# Battery_Load_Share_V1.net
KiCad netlist of a schematic drawn in Altium Designer
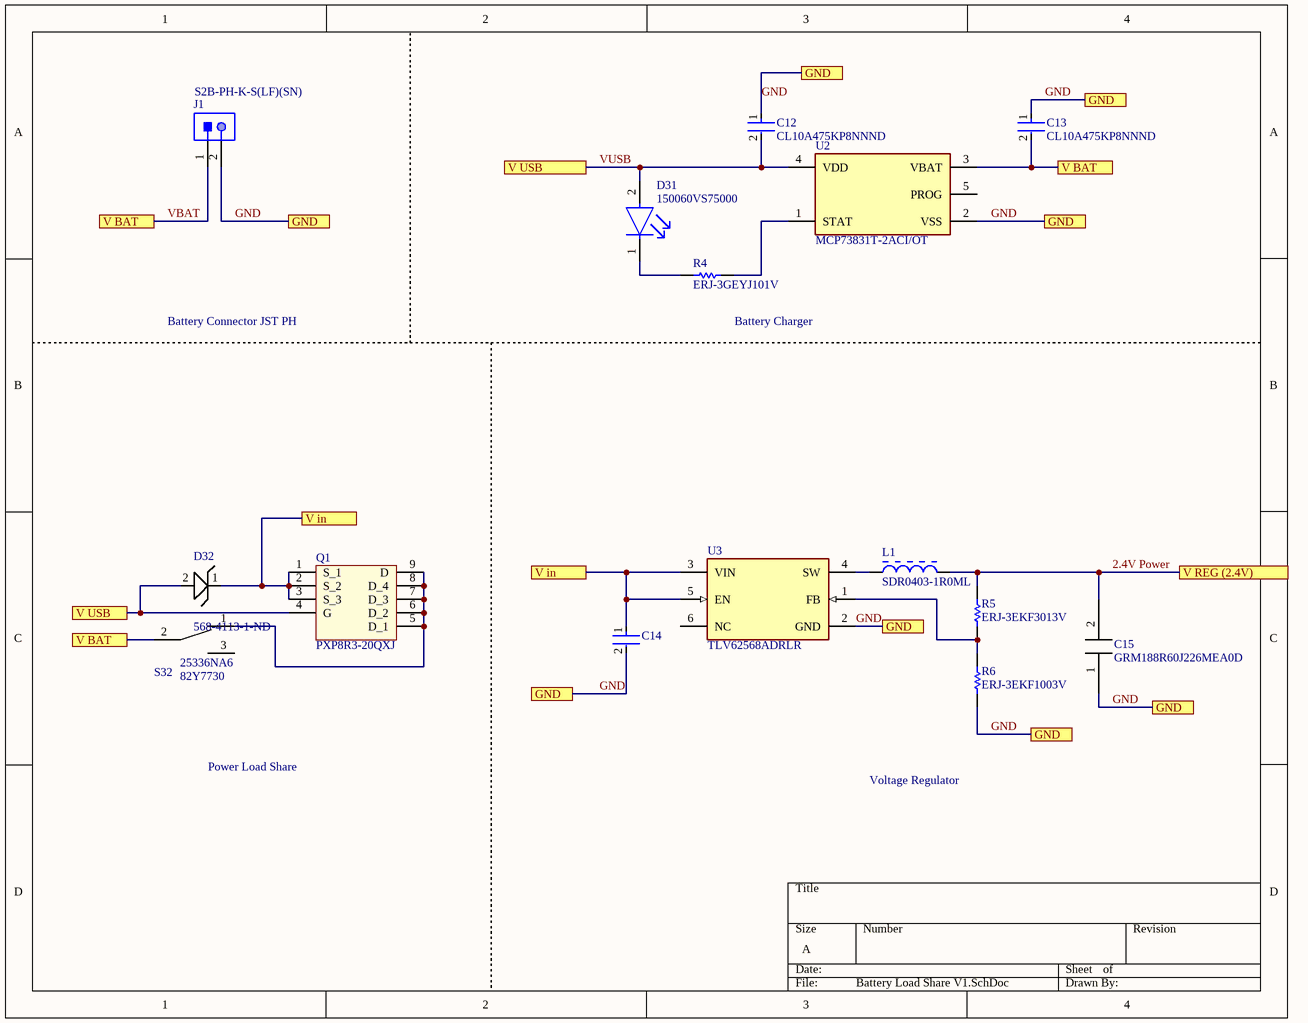
[diagram p0: Battery Load Share V1.SchDoc]

(export (version "E")
  (design (tool "Eeschema 10.0.6"))
  (components
    (comp (ref "C12")
      (value "CL10A475KP8NNND")
      (footprint "FP-CL10-IPC_C")
      (description "Cap Ceramic 4.7uF 10V X5R ±10% Pad SMD 0603 +85°C T/R")
      (fields (field (name "TOLERANCE") "10%"))
      (libsource (lib "Altium Content Vault") (part "b4654b650e69147ec39a6b967a45e02"))
    )
    (comp (ref "C13")
      (value "CL10A475KP8NNND")
      (footprint "FP-CL10-IPC_C")
      (description "Cap Ceramic 4.7uF 10V X5R ±10% Pad SMD 0603 +85°C T/R")
      (fields (field (name "TOLERANCE") "10%"))
      (libsource (lib "Altium Content Vault") (part "b4654b650e69147ec39a6b967a45e02"))
    )
    (comp (ref "C14")
      (value "C1608X7S1A475K080AC")
      (footprint "FP-C1608-080-MFG")
      (description "CAP CER 4.7UF 10V X7S 0603")
      (fields (field (name "TOLERANCE") "10%"))
      (libsource (lib "Altium Content Vault") (part "b4654b650e69147ec39a6b967a45e02"))
    )
    (comp (ref "C15")
      (value "GRM188R60J226MEA0D")
      (footprint "GRM188R60J226MEA0D")
      (description "0603 22 uF 6.3 V ±20% Tolerance X5R SMT Multilayer Ceramic Capacitor")
      (fields (field (name "MANUFACTURER") "Murata") (field (name "TOLERANCE") "20%"))
      (libsource (lib "Universal Parts") (part "GRM188R60J226MEA0D"))
    )
    (comp (ref "D31")
      (value "150060VS75000")
      (footprint "FP-150060VS75000-MFG")
      (description "LED GREEN CLEAR 0603 SMD")
      (libsource (lib "Altium Content Vault") (part "8706943c75ba83719d021d2fdc84c58"))
    )
    (comp (ref "D32")
      (value "PMEG2010AEJ115")
      (footprint "PMEG2010AEJ")
      (fields
        (field (name "MANUFACTURER") "NXP Semiconductors")
        (field (name "SUPPLIER PART NUMBER 1") "568-4113-1-ND")
      )
      (libsource (lib "Universal Parts") (part "PMEG2010AEJ115"))
    )
    (comp (ref "J1")
      (value "S2B-PH-K-S(LF)(SN)")
      (footprint "JST-S2B-PH-K-S_V")
      (fields (field (name "TOLERANCE") "20%"))
      (libsource (lib "Altium Content Vault") (part "CN-1P-M-R2"))
    )
    (comp (ref "L1")
      (value "SDR0403-1R0ML")
      (footprint "BOUR-SDR0403-2_V")
      (fields (field (name "MANUFACTURER") "Bourns"))
      (libsource (lib "Altium Content Vault") (part "BOUR-IND-2A"))
    )
    (comp (ref "Q1")
      (value "PXP8R3-20QXJ")
      (footprint "PXP8R3-20QXJ")
      (description "PXP8R3-20QX - 20 V, P-channel Trench MOSFET")
      (fields (field (name "MANUFACTURER") "Nexperia") (field (name "SUPPLIER PART NUMBER 1") "PXP8R3-20QXJ"))
      (libsource (lib "Universal Parts") (part "PXP8R3-20QXJ"))
    )
    (comp (ref "R4")
      (value "ERJ-3GEYJ101V")
      (footprint "RESC1608X55X30LL15T15")
      (fields (field (name "MANUFACTURER") "Panasonic"))
      (libsource (lib "Altium Content Vault") (part "RES"))
    )
    (comp (ref "R5")
      (value "ERJ-3EKF3013V")
      (footprint "RESC1608X55X30ML15T15")
      (fields (field (name "MANUFACTURER") "Panasonic"))
      (libsource (lib "Altium Content Vault") (part "RES"))
    )
    (comp (ref "R6")
      (value "ERJ-3EKF1003V")
      (footprint "RESC1608X55X30ML15T15")
      (fields (field (name "MANUFACTURER") "Panasonic"))
      (libsource (lib "Altium Content Vault") (part "RES"))
    )
    (comp (ref "S32")
      (value "25336NA6")
      (footprint "25336NA6")
      (description "Switch Slide ON ON SPDT Side Slide 1A 30VDC 20000Cycles PC Pins Thru-Hole")
      (fields (field (name "MANUFACTURER") "APEM") (field (name "SUPPLIER PART NUMBER 1") "82Y7730"))
      (libsource (lib "Universal Parts") (part "25336NA6"))
    )
    (comp (ref "U2")
      (value "MCP73831T-2ACI/OT")
      (footprint "FP-C04-091-OT-IPC_B")
      (description "IC CONTROLLR LI-ION 4.2V SOT23-5")
      (libsource (lib "Altium Content Vault") (part "61f5a3bb3429d9e0caadea342aa3b19"))
    )
    (comp (ref "U3")
      (value "TLV62568ADRLR")
      (footprint "FP-DRL0006A-MFG")
      (description "IC REG BUCK ADJUSTABLE 2A SOT563")
      (libsource (lib "Altium Content Vault") (part "c065b8f3016c1e0e14a773cb518fcf3"))
    )
  )
  (nets
    (net (code "1") (name "/2.4V Power") (class "Default")
      (node (ref "C15") (pin "2") (pinfunction "B_2") (pintype "passive"))
      (node (ref "L1") (pin "2") (pinfunction "2_2") (pintype "passive"))
      (node (ref "R5") (pin "2") (pinfunction "2_2") (pintype "passive"))
    )
    (net (code "2") (name "/GND") (class "Default")
      (node (ref "C12") (pin "1") (pinfunction "1_1") (pintype "passive"))
      (node (ref "C13") (pin "1") (pinfunction "1_1") (pintype "passive"))
      (node (ref "C14") (pin "2") (pinfunction "2_2") (pintype "passive"))
      (node (ref "C15") (pin "1") (pinfunction "B_1") (pintype "passive"))
      (node (ref "J1") (pin "2") (pinfunction "2_2") (pintype "passive"))
      (node (ref "R6") (pin "1") (pinfunction "1_1") (pintype "passive"))
      (node (ref "U2") (pin "2") (pinfunction "VSS_2") (pintype "power_in"))
      (node (ref "U3") (pin "2") (pinfunction "GND_2") (pintype "power_in"))
    )
    (net (code "3") (name "/V in") (class "Default")
      (node (ref "C14") (pin "1") (pinfunction "1_1") (pintype "passive"))
      (node (ref "D32") (pin "1") (pinfunction "34_1") (pintype "passive"))
      (node (ref "Q1") (pin "1") (pinfunction "S_1_1") (pintype "passive"))
      (node (ref "Q1") (pin "2") (pinfunction "S_2_2") (pintype "passive"))
      (node (ref "Q1") (pin "3") (pinfunction "S_3_3") (pintype "passive"))
      (node (ref "U3") (pin "3") (pinfunction "VIN_3") (pintype "power_in"))
      (node (ref "U3") (pin "5") (pinfunction "EN_5") (pintype "input"))
    )
    (net (code "4") (name "/VBAT") (class "Default")
      (node (ref "C13") (pin "2") (pinfunction "2_2") (pintype "passive"))
      (node (ref "J1") (pin "1") (pinfunction "1_1") (pintype "passive"))
      (node (ref "S32") (pin "2") (pinfunction "1_2") (pintype "passive"))
      (node (ref "U2") (pin "3") (pinfunction "VBAT_3") (pintype "power_in"))
    )
    (net (code "5") (name "/VUSB") (class "Default")
      (node (ref "C12") (pin "2") (pinfunction "2_2") (pintype "passive"))
      (node (ref "D31") (pin "2") (pinfunction "A_2") (pintype "passive"))
      (node (ref "D32") (pin "2") (pinfunction "35_2") (pintype "passive"))
      (node (ref "Q1") (pin "4") (pinfunction "G_4") (pintype "passive"))
      (node (ref "U2") (pin "4") (pinfunction "VDD_4") (pintype "power_in"))
    )
    (net (code "6") (name "Net-(D31-C)") (class "Default")
      (node (ref "D31") (pin "1") (pinfunction "C_1") (pintype "passive"))
      (node (ref "R4") (pin "1") (pinfunction "1_1") (pintype "passive"))
    )
    (net (code "7") (name "Net-(Q1-D)") (class "Default")
      (node (ref "Q1") (pin "5") (pinfunction "D_1_5") (pintype "passive"))
      (node (ref "Q1") (pin "6") (pinfunction "D_2_6") (pintype "passive"))
      (node (ref "Q1") (pin "7") (pinfunction "D_3_7") (pintype "passive"))
      (node (ref "Q1") (pin "8") (pinfunction "D_4_8") (pintype "passive"))
      (node (ref "Q1") (pin "9") (pinfunction "D_9") (pintype "passive"))
      (node (ref "S32") (pin "1") (pinfunction "1_1") (pintype "passive"))
    )
    (net (code "8") (name "Net-(U2-STAT)") (class "Default")
      (node (ref "R4") (pin "2") (pinfunction "2_2") (pintype "passive"))
      (node (ref "U2") (pin "1") (pinfunction "STAT_1") (pintype "passive"))
    )
    (net (code "9") (name "Net-(U3-FB)") (class "Default")
      (node (ref "R5") (pin "1") (pinfunction "1_1") (pintype "passive"))
      (node (ref "R6") (pin "2") (pinfunction "2_2") (pintype "passive"))
      (node (ref "U3") (pin "1") (pinfunction "FB_1") (pintype "input"))
    )
    (net (code "10") (name "Net-(U3-SW)") (class "Default")
      (node (ref "L1") (pin "1") (pinfunction "1_1") (pintype "passive"))
      (node (ref "U3") (pin "4") (pinfunction "SW_4") (pintype "passive"))
    )
    (net (code "11") (name "unconnected-(S32-Pad3)") (class "Default")
      (node (ref "S32") (pin "3") (pinfunction "3_3") (pintype "passive"))
    )
    (net (code "12") (name "unconnected-(U2-PROG-Pad5)") (class "Default")
      (node (ref "U2") (pin "5") (pinfunction "PROG_5") (pintype "passive"))
    )
    (net (code "13") (name "unconnected-(U3-NC-Pad6)") (class "Default")
      (node (ref "U3") (pin "6") (pinfunction "NC_6") (pintype "passive"))
    )
  )
)
